# tritiled22_cr2354_lux_c_reverse.net
KiCad netlist of a schematic drawn in EAGLE
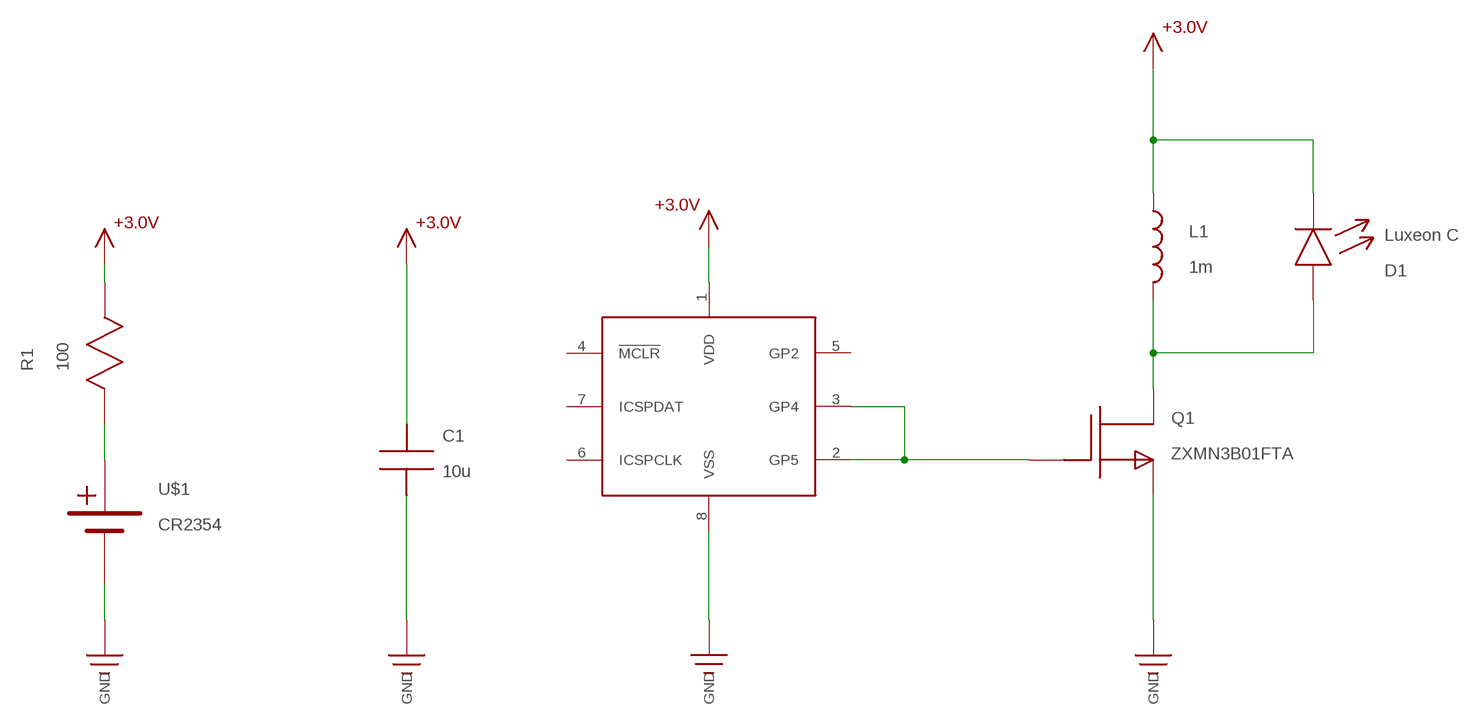
[diagram p0: schematic, sheet 1]

(export (version "E")
  (design (tool "Eeschema 10.0.6"))
  (components
    (comp (ref "C1")
      (value "10u")
      (footprint "eagle-import:1206")
      (libsource (lib "eagle-import") (part "C1206"))
    )
    (comp (ref "D1")
      (value "Luxeon C")
      (footprint "eagle-import:LUXEON_C")
      (libsource (lib "eagle-import") (part "LEDLUXEON_C"))
    )
    (comp (ref "L1")
      (value "1m")
      (footprint "eagle-import:SRR6028_INDUCTOR")
      (libsource (lib "eagle-import") (part "SRR6028_INDUCTOR"))
    )
    (comp (ref "Q1")
      (value "ZXMN3B01FTA")
      (footprint "eagle-import:SOT-23")
      (libsource (lib "eagle-import") (part "ZXMN3B01FSOT23"))
    )
    (comp (ref "R1")
      (value "100")
      (footprint "eagle-import:R1206")
      (libsource (lib "eagle-import") (part "R1206"))
    )
    (comp (ref "U$1")
      (value "CR2354")
      (footprint "eagle-import:CR2354_TABBED")
      (libsource (lib "eagle-import") (part "CR2354_TABBED"))
    )
    (comp (ref "U1")
      (value "PIC12LF1571")
      (footprint "eagle-import:SOIC8")
      (libsource (lib "eagle-import") (part "PIC12LF1571"))
    )
  )
  (nets
    (net (code "1") (name "+3.0V") (class "Default")
      (node (ref "C1") (pin "P$1") (pinfunction "P$1_P$1") (pintype "bidirectional"))
      (node (ref "D1") (pin "C") (pinfunction "C_C") (pintype "bidirectional"))
      (node (ref "L1") (pin "P$1") (pinfunction "1_P$1") (pintype "passive"))
      (node (ref "R1") (pin "P$2") (pinfunction "P$2_P$2") (pintype "bidirectional"))
      (node (ref "U1") (pin "1") (pinfunction "VDD_1") (pintype "bidirectional"))
    )
    (net (code "2") (name "GND") (class "Default")
      (node (ref "C1") (pin "P$2") (pinfunction "P$2_P$2") (pintype "bidirectional"))
      (node (ref "Q1") (pin "2") (pinfunction "S_2") (pintype "bidirectional"))
      (node (ref "U$1") (pin "GND") (pinfunction "0V_GND") (pintype "power_in"))
      (node (ref "U1") (pin "8") (pinfunction "VSS_8") (pintype "bidirectional"))
    )
    (net (code "3") (name "Net-(L1-2)") (class "Default")
      (node (ref "D1") (pin "A") (pinfunction "A_A") (pintype "bidirectional"))
      (node (ref "L1") (pin "P$2") (pinfunction "2_P$2") (pintype "passive"))
      (node (ref "Q1") (pin "3") (pinfunction "D_3") (pintype "bidirectional"))
    )
    (net (code "4") (name "Net-(Q1-G)") (class "Default")
      (node (ref "Q1") (pin "1") (pinfunction "G_1") (pintype "bidirectional"))
      (node (ref "U1") (pin "2") (pinfunction "GP5_2") (pintype "bidirectional"))
      (node (ref "U1") (pin "3") (pinfunction "GP4_3") (pintype "bidirectional"))
    )
    (net (code "5") (name "Net-(U$1-+V)") (class "Default")
      (node (ref "R1") (pin "P$1") (pinfunction "P$1_P$1") (pintype "bidirectional"))
      (node (ref "U$1") (pin "+3V") (pinfunction "+V_+3V") (pintype "power_in"))
    )
    (net (code "6") (name "unconnected-(U1-GP2-Pad5)") (class "Default")
      (node (ref "U1") (pin "5") (pinfunction "GP2_5") (pintype "bidirectional"))
    )
    (net (code "7") (name "unconnected-(U1-ICSPCLK-Pad6)") (class "Default")
      (node (ref "U1") (pin "6") (pinfunction "ICSPCLK_6") (pintype "bidirectional"))
    )
    (net (code "8") (name "unconnected-(U1-ICSPDAT-Pad7)") (class "Default")
      (node (ref "U1") (pin "7") (pinfunction "ICSPDAT_7") (pintype "bidirectional"))
    )
    (net (code "9") (name "unconnected-(U1-~{MCLR}-Pad4)") (class "Default")
      (node (ref "U1") (pin "4") (pinfunction "~{MCLR}_4") (pintype "bidirectional"))
    )
  )
)
